# MCU.net
KiCad netlist of a schematic drawn in Altium Designer
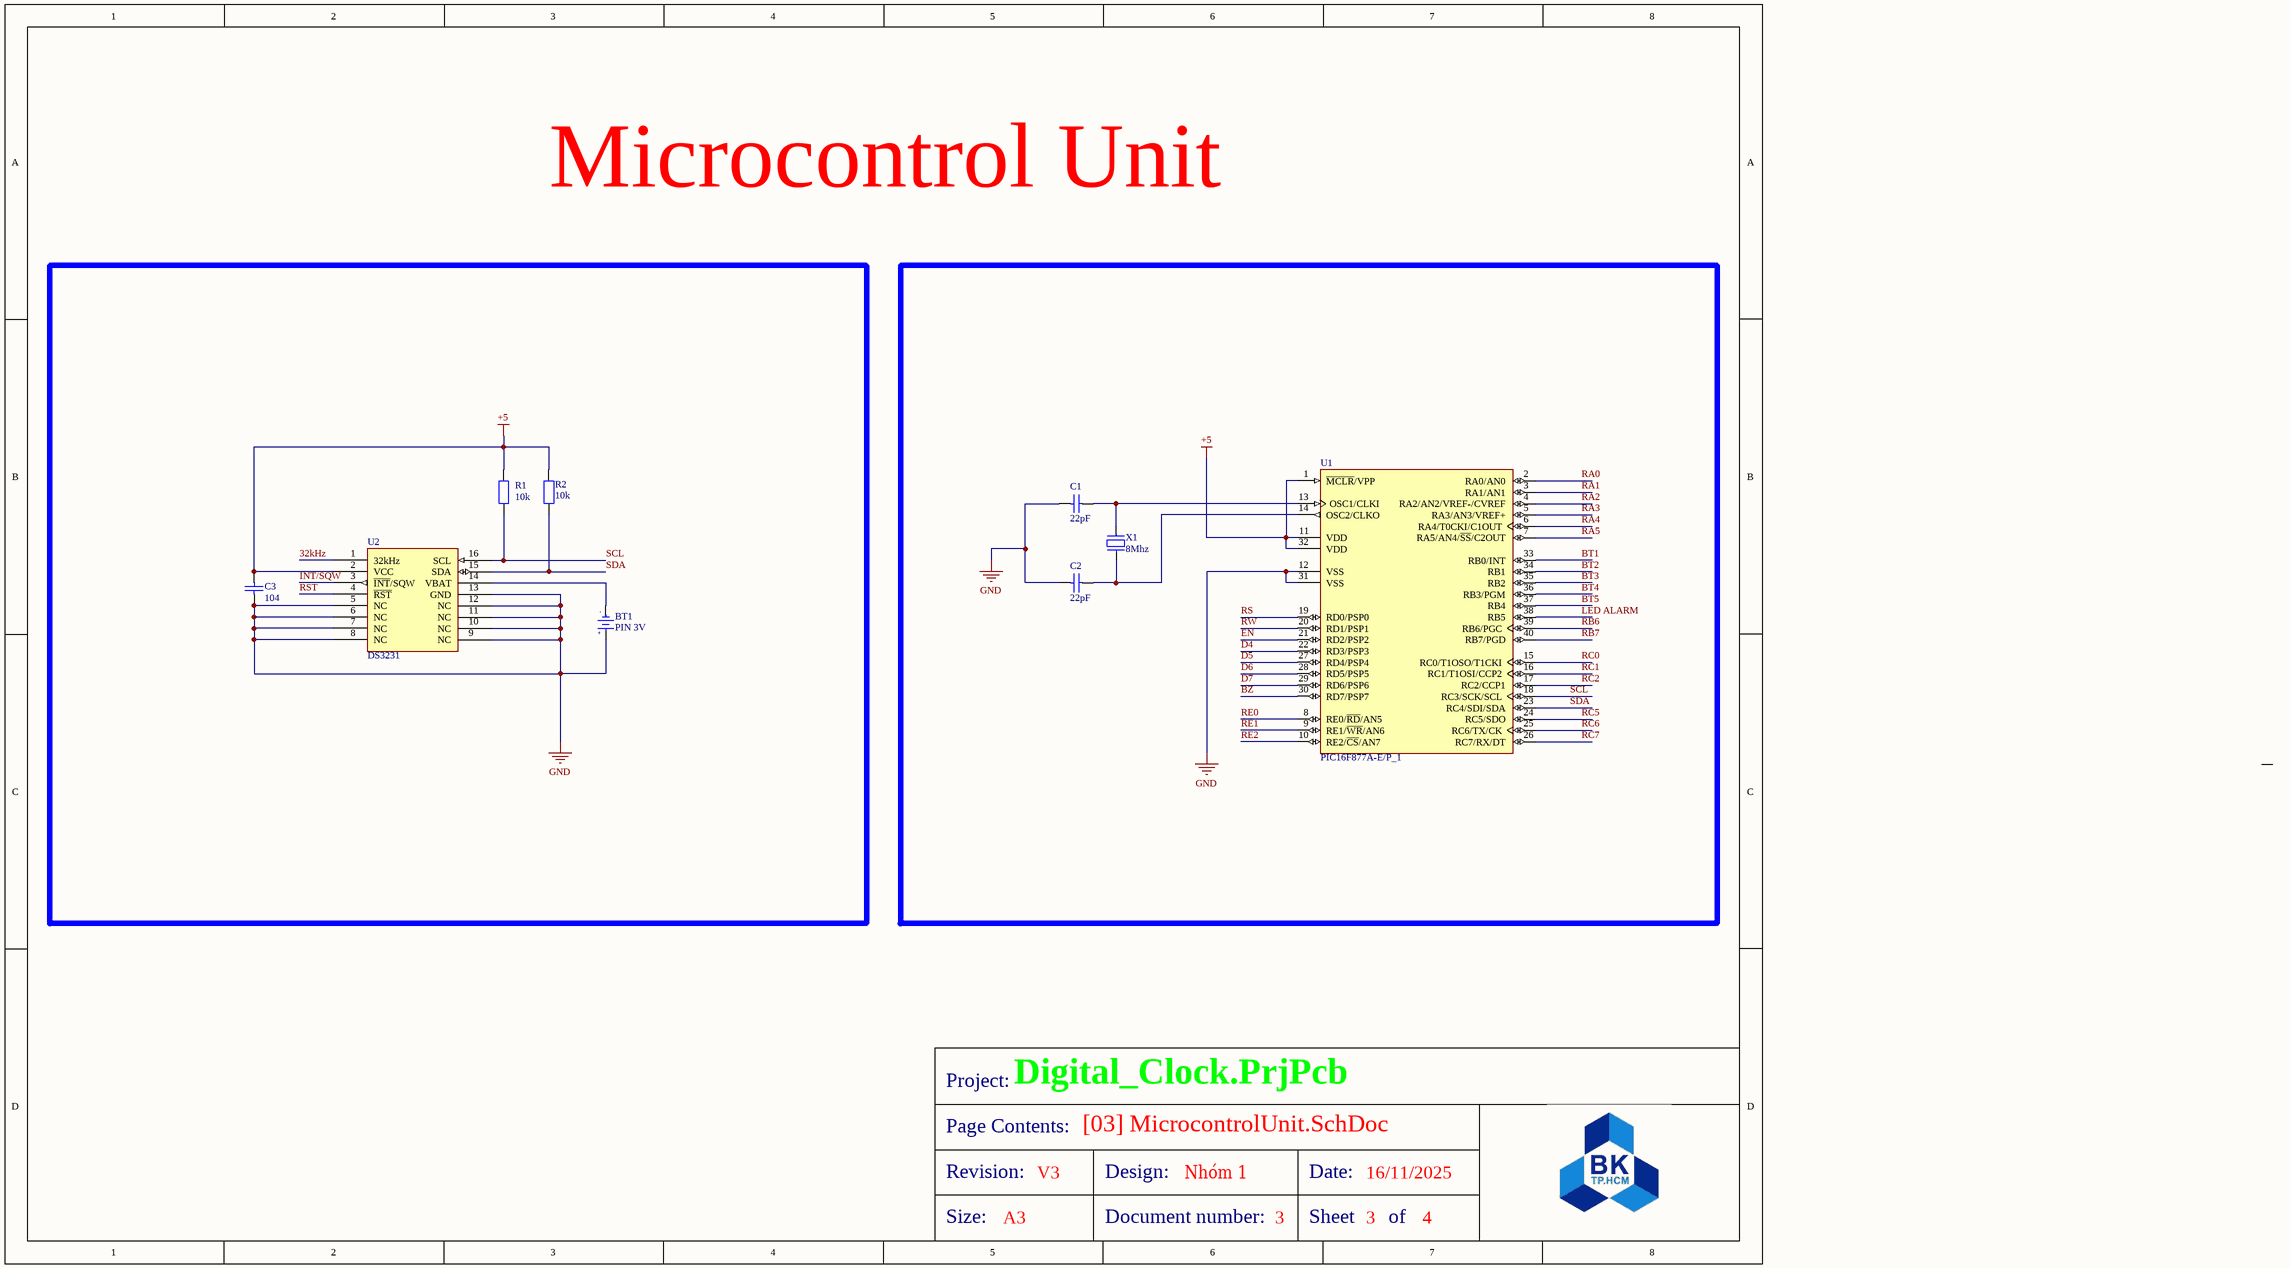
[diagram p0: MCU.SchDoc]

(export (version "E")
  (design (tool "Eeschema 10.0.6"))
  (components
    (comp (ref "BT1")
      (value "PIN 3V")
      (footprint "PIN3V")
      (description "Battery 3VDC")
      (libsource (lib "syhaunguyen") (part "PIN 3V"))
    )
    (comp (ref "C1")
      (value "22pF")
      (footprint "tu gom")
      (description "Cắm")
      (libsource (lib "Capacitor") (part "Tu gom 22pF 50V"))
    )
    (comp (ref "C2")
      (value "22pF")
      (footprint "tu gom")
      (description "Cắm")
      (libsource (lib "Capacitor") (part "Tu gom 22pF 50V"))
    )
    (comp (ref "C3")
      (value "104")
      (footprint "tu gom")
      (description "Cắm")
      (libsource (lib "Capacitor") (part "Tu gom 104 50V"))
    )
    (comp (ref "R1")
      (value "10k")
      (footprint "tro smd 0603")
      (description "Căm")
      (libsource (lib "Resistor") (part "Tro Vach 1/4W 5% 10k"))
    )
    (comp (ref "R2")
      (value "10k")
      (footprint "tro smd 0603")
      (description "Căm")
      (libsource (lib "Resistor") (part "Tro Vach 1/4W 5% 10k"))
    )
    (comp (ref "U1")
      (value "PIC16F877A-E/P_1")
      (footprint "PDIP600-P40")
      (fields (field (name "PUBLISHER") "Altium Limited"))
      (libsource (lib "Cty1") (part "PIC16F877A-E/P_1"))
    )
    (comp (ref "U2") (value "DS3231") (footprint "SL3016") (libsource (lib "My Library") (part "DS3231")))
    (comp (ref "X1")
      (value "8Mhz")
      (footprint "XT2")
      (description "Crystal For all Crystal 2pin.")
      (libsource (lib "syhaunguyen") (part "XT2"))
    )
  )
  (nets
    (net (code "1") (name "+5") (class "Default")
      (node (ref "C3") (pin "1") (pinfunction "1_1") (pintype "passive"))
      (node (ref "R1") (pin "2") (pinfunction "2_2") (pintype "passive"))
      (node (ref "R2") (pin "2") (pinfunction "2_2") (pintype "passive"))
      (node (ref "U1") (pin "1") (pinfunction "~{MCLR}/VPP_1") (pintype "input"))
      (node (ref "U1") (pin "11") (pinfunction "VDD_11") (pintype "power_in"))
      (node (ref "U1") (pin "32") (pinfunction "VDD_32") (pintype "power_in"))
      (node (ref "U2") (pin "2") (pinfunction "VCC_2") (pintype "passive"))
    )
    (net (code "2") (name "/32kHz") (class "Default")
      (node (ref "U2") (pin "1") (pinfunction "32kHz_1") (pintype "passive"))
    )
    (net (code "3") (name "/BT1") (class "Default")
      (node (ref "U1") (pin "33") (pinfunction "RB0/INT_33") (pintype "bidirectional"))
    )
    (net (code "4") (name "/BT2") (class "Default")
      (node (ref "U1") (pin "34") (pinfunction "RB1_34") (pintype "bidirectional"))
    )
    (net (code "5") (name "/BT3") (class "Default")
      (node (ref "U1") (pin "35") (pinfunction "RB2_35") (pintype "bidirectional"))
    )
    (net (code "6") (name "/BT4") (class "Default")
      (node (ref "U1") (pin "36") (pinfunction "RB3/PGM_36") (pintype "bidirectional"))
    )
    (net (code "7") (name "/BT5") (class "Default")
      (node (ref "U1") (pin "37") (pinfunction "RB4_37") (pintype "bidirectional"))
    )
    (net (code "8") (name "/BZ") (class "Default")
      (node (ref "U1") (pin "30") (pinfunction "RD7/PSP7_30") (pintype "bidirectional"))
    )
    (net (code "9") (name "/D4") (class "Default")
      (node (ref "U1") (pin "22") (pinfunction "RD3/PSP3_22") (pintype "bidirectional"))
    )
    (net (code "10") (name "/D5") (class "Default")
      (node (ref "U1") (pin "27") (pinfunction "RD4/PSP4_27") (pintype "bidirectional"))
    )
    (net (code "11") (name "/D6") (class "Default")
      (node (ref "U1") (pin "28") (pinfunction "RD5/PSP5_28") (pintype "bidirectional"))
    )
    (net (code "12") (name "/D7") (class "Default")
      (node (ref "U1") (pin "29") (pinfunction "RD6/PSP6_29") (pintype "bidirectional"))
    )
    (net (code "13") (name "/EN") (class "Default")
      (node (ref "U1") (pin "21") (pinfunction "RD2/PSP2_21") (pintype "bidirectional"))
    )
    (net (code "14") (name "/INT{slash}SQW") (class "Default")
      (node (ref "U2") (pin "3") (pinfunction "~{INT}/SQW_3") (pintype "output"))
    )
    (net (code "15") (name "/LED ALARM") (class "Default")
      (node (ref "U1") (pin "38") (pinfunction "RB5_38") (pintype "bidirectional"))
    )
    (net (code "16") (name "/RA0") (class "Default")
      (node (ref "U1") (pin "2") (pinfunction "RA0/AN0_2") (pintype "bidirectional"))
    )
    (net (code "17") (name "/RA1") (class "Default")
      (node (ref "U1") (pin "3") (pinfunction "RA1/AN1_3") (pintype "bidirectional"))
    )
    (net (code "18") (name "/RA2") (class "Default")
      (node (ref "U1") (pin "4") (pinfunction "RA2/AN2/VREF-/CVREF_4") (pintype "bidirectional"))
    )
    (net (code "19") (name "/RA3") (class "Default")
      (node (ref "U1") (pin "5") (pinfunction "RA3/AN3/VREF+_5") (pintype "bidirectional"))
    )
    (net (code "20") (name "/RA4") (class "Default")
      (node (ref "U1") (pin "6") (pinfunction "RA4/T0CKI/C1OUT_6") (pintype "bidirectional"))
    )
    (net (code "21") (name "/RA5") (class "Default")
      (node (ref "U1") (pin "7") (pinfunction "RA5/AN4/~{SS}/C2OUT_7") (pintype "bidirectional"))
    )
    (net (code "22") (name "/RB6") (class "Default")
      (node (ref "U1") (pin "39") (pinfunction "RB6/PGC_39") (pintype "bidirectional"))
    )
    (net (code "23") (name "/RB7") (class "Default")
      (node (ref "U1") (pin "40") (pinfunction "RB7/PGD_40") (pintype "bidirectional"))
    )
    (net (code "24") (name "/RC0") (class "Default")
      (node (ref "U1") (pin "15") (pinfunction "RC0/T1OSO/T1CKI_15") (pintype "bidirectional"))
    )
    (net (code "25") (name "/RC1") (class "Default")
      (node (ref "U1") (pin "16") (pinfunction "RC1/T1OSI/CCP2_16") (pintype "bidirectional"))
    )
    (net (code "26") (name "/RC2") (class "Default")
      (node (ref "U1") (pin "17") (pinfunction "RC2/CCP1_17") (pintype "bidirectional"))
    )
    (net (code "27") (name "/RC5") (class "Default")
      (node (ref "U1") (pin "24") (pinfunction "RC5/SDO_24") (pintype "bidirectional"))
    )
    (net (code "28") (name "/RC6") (class "Default")
      (node (ref "U1") (pin "25") (pinfunction "RC6/TX/CK_25") (pintype "bidirectional"))
    )
    (net (code "29") (name "/RC7") (class "Default")
      (node (ref "U1") (pin "26") (pinfunction "RC7/RX/DT_26") (pintype "bidirectional"))
    )
    (net (code "30") (name "/RE0") (class "Default")
      (node (ref "U1") (pin "8") (pinfunction "RE0/~{RD}/AN5_8") (pintype "bidirectional"))
    )
    (net (code "31") (name "/RE1") (class "Default")
      (node (ref "U1") (pin "9") (pinfunction "RE1/~{WR}/AN6_9") (pintype "bidirectional"))
    )
    (net (code "32") (name "/RE2") (class "Default")
      (node (ref "U1") (pin "10") (pinfunction "RE2/~{CS}/AN7_10") (pintype "bidirectional"))
    )
    (net (code "33") (name "/RS") (class "Default")
      (node (ref "U1") (pin "19") (pinfunction "RD0/PSP0_19") (pintype "bidirectional"))
    )
    (net (code "34") (name "/RST") (class "Default")
      (node (ref "U2") (pin "4") (pinfunction "~{RST}_4") (pintype "passive"))
    )
    (net (code "35") (name "/RW") (class "Default")
      (node (ref "U1") (pin "20") (pinfunction "RD1/PSP1_20") (pintype "bidirectional"))
    )
    (net (code "36") (name "/SCL") (class "Default")
      (node (ref "R1") (pin "1") (pinfunction "1_1") (pintype "passive"))
      (node (ref "U1") (pin "18") (pinfunction "RC3/SCK/SCL_18") (pintype "bidirectional"))
      (node (ref "U2") (pin "16") (pinfunction "SCL_16") (pintype "input"))
    )
    (net (code "37") (name "/SDA") (class "Default")
      (node (ref "R2") (pin "1") (pinfunction "1_1") (pintype "passive"))
      (node (ref "U1") (pin "23") (pinfunction "RC4/SDI/SDA_23") (pintype "bidirectional"))
      (node (ref "U2") (pin "15") (pinfunction "SDA_15") (pintype "bidirectional"))
    )
    (net (code "38") (name "GND") (class "Default")
      (node (ref "BT1") (pin "1") (pinfunction "+3V_1") (pintype "passive"))
      (node (ref "C1") (pin "2") (pinfunction "2_2") (pintype "passive"))
      (node (ref "C2") (pin "2") (pinfunction "2_2") (pintype "passive"))
      (node (ref "C3") (pin "2") (pinfunction "2_2") (pintype "passive"))
      (node (ref "U1") (pin "12") (pinfunction "VSS_12") (pintype "power_in"))
      (node (ref "U1") (pin "31") (pinfunction "VSS_31") (pintype "power_in"))
      (node (ref "U2") (pin "10") (pinfunction "NC_10") (pintype "passive"))
      (node (ref "U2") (pin "11") (pinfunction "NC_11") (pintype "passive"))
      (node (ref "U2") (pin "12") (pinfunction "NC_12") (pintype "passive"))
      (node (ref "U2") (pin "13") (pinfunction "GND_13") (pintype "passive"))
      (node (ref "U2") (pin "5") (pinfunction "NC_5") (pintype "passive"))
      (node (ref "U2") (pin "6") (pinfunction "NC_6") (pintype "passive"))
      (node (ref "U2") (pin "7") (pinfunction "NC_7") (pintype "passive"))
      (node (ref "U2") (pin "8") (pinfunction "NC_8") (pintype "passive"))
      (node (ref "U2") (pin "9") (pinfunction "NC_9") (pintype "passive"))
    )
    (net (code "39") (name "Net-(BT1-GND)") (class "Default")
      (node (ref "BT1") (pin "2") (pinfunction "GND_2") (pintype "passive"))
      (node (ref "U2") (pin "14") (pinfunction "VBAT_14") (pintype "passive"))
    )
    (net (code "40") (name "Net-(U1-OSC1{slash}CLKI)") (class "Default")
      (node (ref "C1") (pin "1") (pinfunction "1_1") (pintype "passive"))
      (node (ref "U1") (pin "13") (pinfunction "OSC1/CLKI_13") (pintype "input"))
      (node (ref "X1") (pin "1") (pinfunction "1_1") (pintype "passive"))
    )
    (net (code "41") (name "Net-(U1-OSC2{slash}CLKO)") (class "Default")
      (node (ref "C2") (pin "1") (pinfunction "1_1") (pintype "passive"))
      (node (ref "U1") (pin "14") (pinfunction "OSC2/CLKO_14") (pintype "output"))
      (node (ref "X1") (pin "2") (pinfunction "2_2") (pintype "passive"))
    )
  )
)
